# snes-bt2.net
KiCad netlist of a schematic drawn in EAGLE
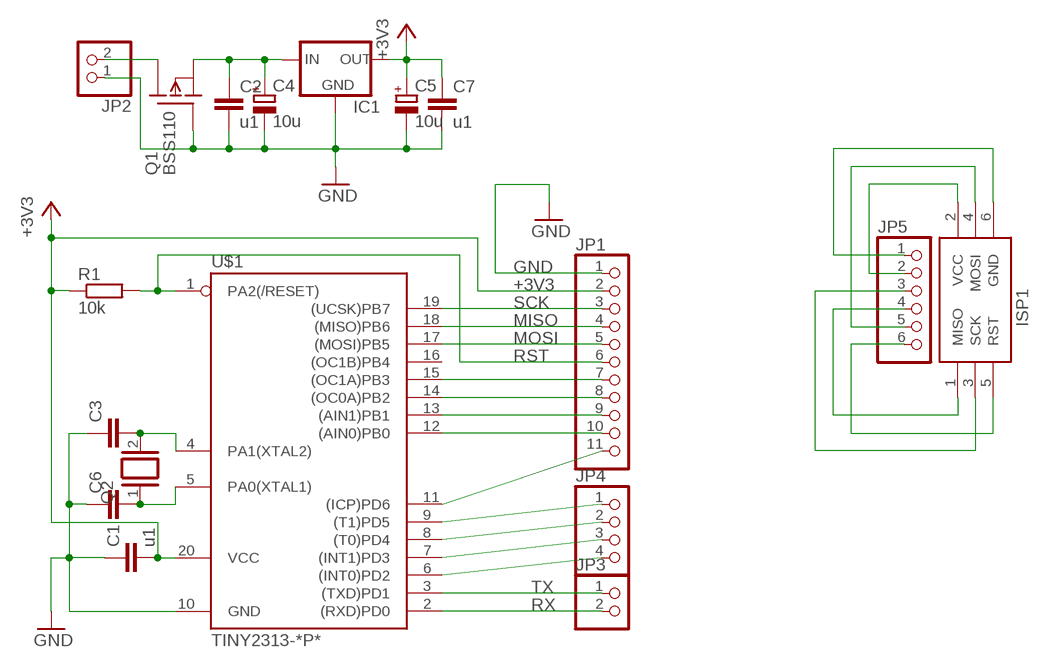
[diagram p0: schematic, sheet 1]

(export (version "E")
  (design (tool "Eeschema 10.0.6"))
  (components
    (comp (ref "C1")
      (value "u1")
      (footprint "eagle-import:C025-025X050")
      (libsource (lib "eagle-import") (part "C-EU025-025X050"))
    )
    (comp (ref "C2")
      (value "u1")
      (footprint "eagle-import:C025-025X050")
      (libsource (lib "eagle-import") (part "C-EU025-025X050"))
    )
    (comp (ref "C3")
      (value "C-EUC0805K")
      (footprint "eagle-import:C0805K")
      (libsource (lib "eagle-import") (part "C-EUC0805K"))
    )
    (comp (ref "C4")
      (value "10u")
      (footprint "eagle-import:E2,5-6E")
      (libsource (lib "eagle-import") (part "CPOL-EUE2,5-6E"))
    )
    (comp (ref "C5")
      (value "10u")
      (footprint "eagle-import:E2,5-6E")
      (libsource (lib "eagle-import") (part "CPOL-EUE2,5-6E"))
    )
    (comp (ref "C6")
      (value "C-EUC0805K")
      (footprint "eagle-import:C0805K")
      (libsource (lib "eagle-import") (part "C-EUC0805K"))
    )
    (comp (ref "C7")
      (value "u1")
      (footprint "eagle-import:C025-025X050")
      (libsource (lib "eagle-import") (part "C-EU025-025X050"))
    )
    (comp (ref "IC1")
      (value "MCP1700_TO92-THIN")
      (footprint "eagle-import:TO-92")
      (libsource (lib "eagle-import") (part "MCP1700_TO92-THIN"))
    )
    (comp (ref "ISP1")
      (value "AVRISP-6")
      (footprint "eagle-import:AVRISP")
      (libsource (lib "eagle-import") (part "AVRISP-6"))
    )
    (comp (ref "JP1")
      (value "PINHD-1X11")
      (footprint "eagle-import:1X11")
      (libsource (lib "eagle-import") (part "PINHD-1X11"))
    )
    (comp (ref "JP2")
      (value "PINHD-1X2")
      (footprint "eagle-import:1X02")
      (libsource (lib "eagle-import") (part "PINHD-1X2"))
    )
    (comp (ref "JP3")
      (value "PINHD-1X2")
      (footprint "eagle-import:1X02")
      (libsource (lib "eagle-import") (part "PINHD-1X2"))
    )
    (comp (ref "JP4")
      (value "PINHD-1X4")
      (footprint "eagle-import:1X04")
      (libsource (lib "eagle-import") (part "PINHD-1X4"))
    )
    (comp (ref "JP5")
      (value "PINHD-1X6")
      (footprint "eagle-import:1X06")
      (libsource (lib "eagle-import") (part "PINHD-1X6"))
    )
    (comp (ref "Q1")
      (value "BSS110")
      (footprint "eagle-import:TO92")
      (libsource (lib "eagle-import") (part "BSS110"))
    )
    (comp (ref "Q2")
      (value "XTAL/S")
      (footprint "eagle-import:QS")
      (libsource (lib "eagle-import") (part "XTAL/S"))
    )
    (comp (ref "R1")
      (value "10k")
      (footprint "eagle-import:0204_7")
      (libsource (lib "eagle-import") (part "R-EU_0204/7"))
    )
    (comp (ref "U$1")
      (value "TINY2313-*P*")
      (footprint "eagle-import:DIL20")
      (libsource (lib "eagle-import") (part "TINY2313-P"))
    )
  )
  (nets
    (net (code "1") (name "+3V3") (class "Default")
      (node (ref "C1") (pin "2") (pinfunction "2_2") (pintype "passive"))
      (node (ref "C5") (pin "+") (pinfunction "+_+") (pintype "passive"))
      (node (ref "C7") (pin "1") (pinfunction "1_1") (pintype "passive"))
      (node (ref "IC1") (pin "3") (pinfunction "OUT_3") (pintype "passive"))
      (node (ref "JP1") (pin "2") (pinfunction "2_2") (pintype "passive"))
      (node (ref "R1") (pin "1") (pinfunction "1_1") (pintype "passive"))
      (node (ref "U$1") (pin "20") (pinfunction "VCC_20") (pintype "power_in"))
    )
    (net (code "2") (name "/MISO") (class "Default")
      (node (ref "JP1") (pin "4") (pinfunction "4_4") (pintype "passive"))
      (node (ref "U$1") (pin "18") (pinfunction "(MISO)PB6_18") (pintype "bidirectional"))
    )
    (net (code "3") (name "/MOSI") (class "Default")
      (node (ref "JP1") (pin "5") (pinfunction "5_5") (pintype "passive"))
      (node (ref "U$1") (pin "17") (pinfunction "(MOSI)PB5_17") (pintype "bidirectional"))
    )
    (net (code "4") (name "/RST") (class "Default")
      (node (ref "JP1") (pin "6") (pinfunction "6_6") (pintype "passive"))
      (node (ref "R1") (pin "2") (pinfunction "2_2") (pintype "passive"))
      (node (ref "U$1") (pin "1") (pinfunction "PA2(/RESET)_1") (pintype "input"))
    )
    (net (code "5") (name "/RX") (class "Default")
      (node (ref "JP3") (pin "2") (pinfunction "2_2") (pintype "passive"))
      (node (ref "U$1") (pin "2") (pinfunction "(RXD)PD0_2") (pintype "bidirectional"))
    )
    (net (code "6") (name "/SCK") (class "Default")
      (node (ref "JP1") (pin "3") (pinfunction "3_3") (pintype "passive"))
      (node (ref "U$1") (pin "19") (pinfunction "(UCSK)PB7_19") (pintype "bidirectional"))
    )
    (net (code "7") (name "/TX") (class "Default")
      (node (ref "JP3") (pin "1") (pinfunction "1_1") (pintype "passive"))
      (node (ref "U$1") (pin "3") (pinfunction "(TXD)PD1_3") (pintype "bidirectional"))
    )
    (net (code "8") (name "GND") (class "Default")
      (node (ref "C1") (pin "1") (pinfunction "1_1") (pintype "passive"))
      (node (ref "C2") (pin "2") (pinfunction "2_2") (pintype "passive"))
      (node (ref "C3") (pin "1") (pinfunction "1_1") (pintype "passive"))
      (node (ref "C4") (pin "-") (pinfunction "-_-") (pintype "passive"))
      (node (ref "C5") (pin "-") (pinfunction "-_-") (pintype "passive"))
      (node (ref "C6") (pin "1") (pinfunction "1_1") (pintype "passive"))
      (node (ref "C7") (pin "2") (pinfunction "2_2") (pintype "passive"))
      (node (ref "IC1") (pin "1") (pinfunction "GND_1") (pintype "input"))
      (node (ref "JP1") (pin "1") (pinfunction "1_1") (pintype "passive"))
      (node (ref "JP2") (pin "1") (pinfunction "1_1") (pintype "passive"))
      (node (ref "Q1") (pin "2") (pinfunction "G_2") (pintype "passive"))
      (node (ref "U$1") (pin "10") (pinfunction "GND_10") (pintype "power_in"))
    )
    (net (code "9") (name "Net-(IC1-IN)") (class "Default")
      (node (ref "C2") (pin "1") (pinfunction "1_1") (pintype "passive"))
      (node (ref "C4") (pin "+") (pinfunction "+_+") (pintype "passive"))
      (node (ref "IC1") (pin "2") (pinfunction "IN_2") (pintype "input"))
      (node (ref "Q1") (pin "1") (pinfunction "S_1") (pintype "passive"))
    )
    (net (code "10") (name "Net-(ISP1-GND)") (class "Default")
      (node (ref "ISP1") (pin "6") (pinfunction "GND_6") (pintype "power_in"))
      (node (ref "JP5") (pin "1") (pinfunction "1_1") (pintype "passive"))
    )
    (net (code "11") (name "Net-(ISP1-MISO)") (class "Default")
      (node (ref "ISP1") (pin "1") (pinfunction "MISO_1") (pintype "input"))
      (node (ref "JP5") (pin "4") (pinfunction "4_4") (pintype "passive"))
    )
    (net (code "12") (name "Net-(ISP1-MOSI)") (class "Default")
      (node (ref "ISP1") (pin "4") (pinfunction "MOSI_4") (pintype "output"))
      (node (ref "JP5") (pin "5") (pinfunction "5_5") (pintype "passive"))
    )
    (net (code "13") (name "Net-(ISP1-RST)") (class "Default")
      (node (ref "ISP1") (pin "5") (pinfunction "RST_5") (pintype "output"))
      (node (ref "JP5") (pin "6") (pinfunction "6_6") (pintype "passive"))
    )
    (net (code "14") (name "Net-(ISP1-SCK)") (class "Default")
      (node (ref "ISP1") (pin "3") (pinfunction "SCK_3") (pintype "output"))
      (node (ref "JP5") (pin "3") (pinfunction "3_3") (pintype "passive"))
    )
    (net (code "15") (name "Net-(ISP1-VCC)") (class "Default")
      (node (ref "ISP1") (pin "2") (pinfunction "VCC_2") (pintype "power_in"))
      (node (ref "JP5") (pin "2") (pinfunction "2_2") (pintype "passive"))
    )
    (net (code "16") (name "Net-(Q1-D)") (class "Default")
      (node (ref "JP2") (pin "2") (pinfunction "2_2") (pintype "passive"))
      (node (ref "Q1") (pin "3") (pinfunction "D_3") (pintype "passive"))
    )
    (net (code "17") (name "Net-(U$1-(AIN0)PB0)") (class "Default")
      (node (ref "JP1") (pin "10") (pinfunction "10_10") (pintype "passive"))
      (node (ref "U$1") (pin "12") (pinfunction "(AIN0)PB0_12") (pintype "bidirectional"))
    )
    (net (code "18") (name "Net-(U$1-(AIN1)PB1)") (class "Default")
      (node (ref "JP1") (pin "9") (pinfunction "9_9") (pintype "passive"))
      (node (ref "U$1") (pin "13") (pinfunction "(AIN1)PB1_13") (pintype "bidirectional"))
    )
    (net (code "19") (name "Net-(U$1-(ICP)PD6)") (class "Default")
      (node (ref "JP1") (pin "11") (pinfunction "11_11") (pintype "passive"))
      (node (ref "U$1") (pin "11") (pinfunction "(ICP)PD6_11") (pintype "bidirectional"))
    )
    (net (code "20") (name "Net-(U$1-(INT0)PD2)") (class "Default")
      (node (ref "JP4") (pin "4") (pinfunction "4_4") (pintype "passive"))
      (node (ref "U$1") (pin "6") (pinfunction "(INT0)PD2_6") (pintype "bidirectional"))
    )
    (net (code "21") (name "Net-(U$1-(INT1)PD3)") (class "Default")
      (node (ref "JP4") (pin "3") (pinfunction "3_3") (pintype "passive"))
      (node (ref "U$1") (pin "7") (pinfunction "(INT1)PD3_7") (pintype "bidirectional"))
    )
    (net (code "22") (name "Net-(U$1-(OC0A)PB2)") (class "Default")
      (node (ref "JP1") (pin "8") (pinfunction "8_8") (pintype "passive"))
      (node (ref "U$1") (pin "14") (pinfunction "(OC0A)PB2_14") (pintype "bidirectional"))
    )
    (net (code "23") (name "Net-(U$1-(OC1A)PB3)") (class "Default")
      (node (ref "JP1") (pin "7") (pinfunction "7_7") (pintype "passive"))
      (node (ref "U$1") (pin "15") (pinfunction "(OC1A)PB3_15") (pintype "bidirectional"))
    )
    (net (code "24") (name "Net-(U$1-(T0)PD4)") (class "Default")
      (node (ref "JP4") (pin "2") (pinfunction "2_2") (pintype "passive"))
      (node (ref "U$1") (pin "8") (pinfunction "(T0)PD4_8") (pintype "bidirectional"))
    )
    (net (code "25") (name "Net-(U$1-(T1)PD5)") (class "Default")
      (node (ref "JP4") (pin "1") (pinfunction "1_1") (pintype "passive"))
      (node (ref "U$1") (pin "9") (pinfunction "(T1)PD5_9") (pintype "bidirectional"))
    )
    (net (code "26") (name "Net-(U$1-PA0(XTAL1))") (class "Default")
      (node (ref "C6") (pin "2") (pinfunction "2_2") (pintype "passive"))
      (node (ref "Q2") (pin "1") (pinfunction "1_1") (pintype "passive"))
      (node (ref "U$1") (pin "5") (pinfunction "PA0(XTAL1)_5") (pintype "bidirectional"))
    )
    (net (code "27") (name "Net-(U$1-PA1(XTAL2))") (class "Default")
      (node (ref "C3") (pin "2") (pinfunction "2_2") (pintype "passive"))
      (node (ref "Q2") (pin "2") (pinfunction "2_2") (pintype "passive"))
      (node (ref "U$1") (pin "4") (pinfunction "PA1(XTAL2)_4") (pintype "bidirectional"))
    )
    (net (code "28") (name "unconnected-(U$1-(OC1B)PB4-Pad16)") (class "Default")
      (node (ref "U$1") (pin "16") (pinfunction "(OC1B)PB4_16") (pintype "bidirectional"))
    )
  )
)
